# OSDK_USB-C-2.net
KiCad netlist of a schematic drawn in EAGLE
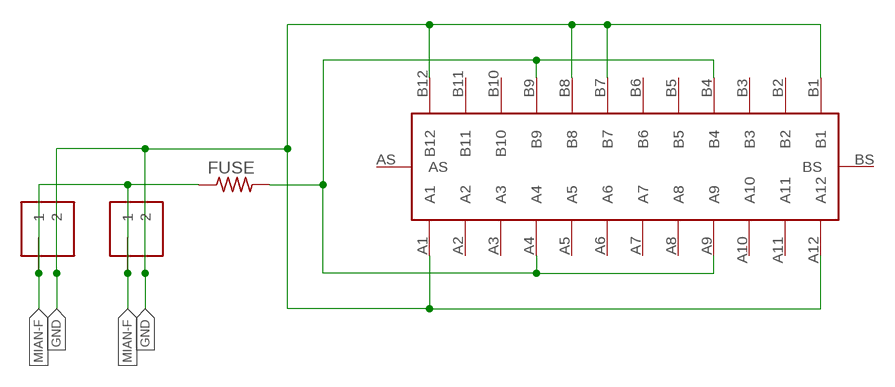
[diagram p0: schematic, sheet 1]

(export (version "E")
  (design (tool "Eeschema 10.0.6"))
  (components
    (comp (ref "CU3124PAAHLA002-NH")
      (value "USB-C")
      (footprint "eagle-import:USB-C")
      (libsource (lib "eagle-import") (part "USB-C"))
    )
    (comp (ref "FUSE")
      (value "R-US_0207/9")
      (footprint "eagle-import:0207_9")
      (libsource (lib "eagle-import") (part "R-US_0207/9"))
    )
    (comp (ref "J1")
      (value "ADAFRUIT_1X2-3.5MM")
      (footprint "eagle-import:ADAFRUIT_1X2-3.5MM")
      (libsource (lib "eagle-import") (part "ADAFRUIT_1X2-3.5MM"))
    )
    (comp (ref "J2")
      (value "ADAFRUIT_1X2-3.5MM")
      (footprint "eagle-import:ADAFRUIT_1X2-3.5MM")
      (libsource (lib "eagle-import") (part "ADAFRUIT_1X2-3.5MM"))
    )
  )
  (nets
    (net (code "1") (name "GND") (class "Default")
      (node (ref "CU3124PAAHLA002-NH") (pin "A1") (pinfunction "A1_A1") (pintype "bidirectional"))
      (node (ref "CU3124PAAHLA002-NH") (pin "A12") (pinfunction "A12_A12") (pintype "bidirectional"))
      (node (ref "CU3124PAAHLA002-NH") (pin "B1") (pinfunction "B1_B1") (pintype "bidirectional"))
      (node (ref "CU3124PAAHLA002-NH") (pin "B12") (pinfunction "B12_B12") (pintype "bidirectional"))
      (node (ref "CU3124PAAHLA002-NH") (pin "B7") (pinfunction "B7_B7") (pintype "bidirectional"))
      (node (ref "CU3124PAAHLA002-NH") (pin "B8") (pinfunction "B8_B8") (pintype "bidirectional"))
      (node (ref "J1") (pin "2") (pinfunction "2_2") (pintype "passive"))
      (node (ref "J2") (pin "2") (pinfunction "2_2") (pintype "passive"))
    )
    (net (code "2") (name "MIAN-F") (class "Default")
      (node (ref "FUSE") (pin "1") (pinfunction "1_1") (pintype "passive"))
      (node (ref "J1") (pin "1") (pinfunction "1_1") (pintype "passive"))
      (node (ref "J2") (pin "1") (pinfunction "1_1") (pintype "passive"))
    )
    (net (code "3") (name "Net-(CU3124PAAHLA002-NH-PadA4)") (class "Default")
      (node (ref "CU3124PAAHLA002-NH") (pin "A4") (pinfunction "A4_A4") (pintype "bidirectional"))
      (node (ref "CU3124PAAHLA002-NH") (pin "A9") (pinfunction "A9_A9") (pintype "bidirectional"))
      (node (ref "CU3124PAAHLA002-NH") (pin "B4") (pinfunction "B4_B4") (pintype "bidirectional"))
      (node (ref "CU3124PAAHLA002-NH") (pin "B9") (pinfunction "B9_B9") (pintype "bidirectional"))
      (node (ref "FUSE") (pin "2") (pinfunction "2_2") (pintype "passive"))
    )
    (net (code "4") (name "unconnected-(CU3124PAAHLA002-NH-PadA2)") (class "Default")
      (node (ref "CU3124PAAHLA002-NH") (pin "A2") (pinfunction "A2_A2") (pintype "bidirectional"))
    )
    (net (code "5") (name "unconnected-(CU3124PAAHLA002-NH-PadA3)") (class "Default")
      (node (ref "CU3124PAAHLA002-NH") (pin "A3") (pinfunction "A3_A3") (pintype "bidirectional"))
    )
    (net (code "6") (name "unconnected-(CU3124PAAHLA002-NH-PadA5)") (class "Default")
      (node (ref "CU3124PAAHLA002-NH") (pin "A5") (pinfunction "A5_A5") (pintype "bidirectional"))
    )
    (net (code "7") (name "unconnected-(CU3124PAAHLA002-NH-PadA6)") (class "Default")
      (node (ref "CU3124PAAHLA002-NH") (pin "A6") (pinfunction "A6_A6") (pintype "bidirectional"))
    )
    (net (code "8") (name "unconnected-(CU3124PAAHLA002-NH-PadA7)") (class "Default")
      (node (ref "CU3124PAAHLA002-NH") (pin "A7") (pinfunction "A7_A7") (pintype "bidirectional"))
    )
    (net (code "9") (name "unconnected-(CU3124PAAHLA002-NH-PadA8)") (class "Default")
      (node (ref "CU3124PAAHLA002-NH") (pin "A8") (pinfunction "A8_A8") (pintype "bidirectional"))
    )
    (net (code "10") (name "unconnected-(CU3124PAAHLA002-NH-PadA10)") (class "Default")
      (node (ref "CU3124PAAHLA002-NH") (pin "A10") (pinfunction "A10_A10") (pintype "bidirectional"))
    )
    (net (code "11") (name "unconnected-(CU3124PAAHLA002-NH-PadA11)") (class "Default")
      (node (ref "CU3124PAAHLA002-NH") (pin "A11") (pinfunction "A11_A11") (pintype "bidirectional"))
    )
    (net (code "12") (name "unconnected-(CU3124PAAHLA002-NH-PadAS)") (class "Default")
      (node (ref "CU3124PAAHLA002-NH") (pin "AS") (pinfunction "AS_AS") (pintype "bidirectional"))
    )
    (net (code "13") (name "unconnected-(CU3124PAAHLA002-NH-PadB2)") (class "Default")
      (node (ref "CU3124PAAHLA002-NH") (pin "B2") (pinfunction "B2_B2") (pintype "bidirectional"))
    )
    (net (code "14") (name "unconnected-(CU3124PAAHLA002-NH-PadB3)") (class "Default")
      (node (ref "CU3124PAAHLA002-NH") (pin "B3") (pinfunction "B3_B3") (pintype "bidirectional"))
    )
    (net (code "15") (name "unconnected-(CU3124PAAHLA002-NH-PadB5)") (class "Default")
      (node (ref "CU3124PAAHLA002-NH") (pin "B5") (pinfunction "B5_B5") (pintype "bidirectional"))
    )
    (net (code "16") (name "unconnected-(CU3124PAAHLA002-NH-PadB6)") (class "Default")
      (node (ref "CU3124PAAHLA002-NH") (pin "B6") (pinfunction "B6_B6") (pintype "bidirectional"))
    )
    (net (code "17") (name "unconnected-(CU3124PAAHLA002-NH-PadB10)") (class "Default")
      (node (ref "CU3124PAAHLA002-NH") (pin "B10") (pinfunction "B10_B10") (pintype "bidirectional"))
    )
    (net (code "18") (name "unconnected-(CU3124PAAHLA002-NH-PadB11)") (class "Default")
      (node (ref "CU3124PAAHLA002-NH") (pin "B11") (pinfunction "B11_B11") (pintype "bidirectional"))
    )
    (net (code "19") (name "unconnected-(CU3124PAAHLA002-NH-PadBS)") (class "Default")
      (node (ref "CU3124PAAHLA002-NH") (pin "BS") (pinfunction "BS_BS") (pintype "bidirectional"))
    )
  )
)
